# soldering_station_controls.net
KiCad netlist of a schematic drawn in Altium Designer
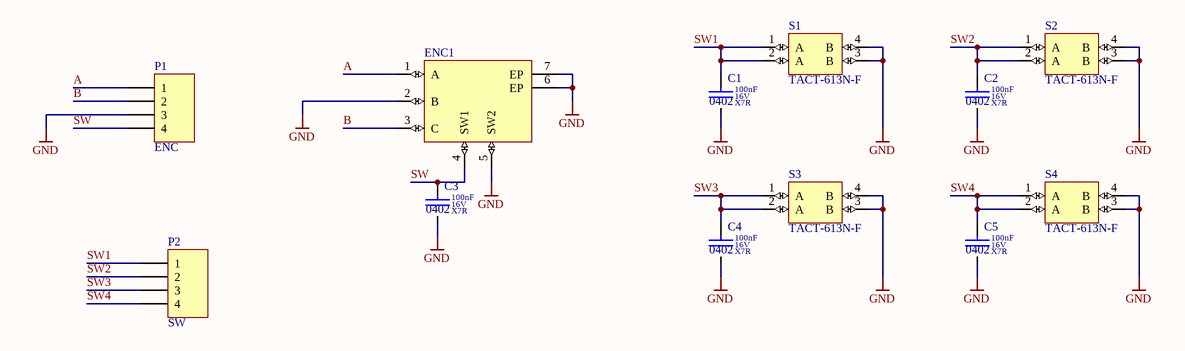
[diagram p0: soldering_station_controls.SchDoc]

(export (version "E")
  (design (tool "Eeschema 10.0.6"))
  (components
    (comp (ref "C1")
      (value "100nF")
      (footprint "C_0402_1005")
      (description "Capacitor")
      (fields
        (field (name "DIELECTRIC") "X7R")
        (field (name "VOLTAGE") "16V")
        (field (name "SCH_FOOTPRINT") "0402")
        (field (name "PART NUMBER") "C_100nF_16V_X7R_0402_10")
        (field (name "MANUFACTURER") "Murata")
      )
      (libsource (lib "Library") (part "C"))
    )
    (comp (ref "C2")
      (value "100nF")
      (footprint "C_0402_1005")
      (description "Capacitor")
      (fields
        (field (name "DIELECTRIC") "X7R")
        (field (name "VOLTAGE") "16V")
        (field (name "SCH_FOOTPRINT") "0402")
        (field (name "PART NUMBER") "C_100nF_16V_X7R_0402_10")
        (field (name "MANUFACTURER") "Murata")
      )
      (libsource (lib "Library") (part "C"))
    )
    (comp (ref "C3")
      (value "100nF")
      (footprint "C_0402_1005")
      (description "Capacitor")
      (fields
        (field (name "DIELECTRIC") "X7R")
        (field (name "VOLTAGE") "16V")
        (field (name "SCH_FOOTPRINT") "0402")
        (field (name "PART NUMBER") "C_100nF_16V_X7R_0402_10")
        (field (name "MANUFACTURER") "Murata")
      )
      (libsource (lib "Library") (part "C"))
    )
    (comp (ref "C4")
      (value "100nF")
      (footprint "C_0402_1005")
      (description "Capacitor")
      (fields
        (field (name "DIELECTRIC") "X7R")
        (field (name "VOLTAGE") "16V")
        (field (name "SCH_FOOTPRINT") "0402")
        (field (name "PART NUMBER") "C_100nF_16V_X7R_0402_10")
        (field (name "MANUFACTURER") "Murata")
      )
      (libsource (lib "Library") (part "C"))
    )
    (comp (ref "C5")
      (value "100nF")
      (footprint "C_0402_1005")
      (description "Capacitor")
      (fields
        (field (name "DIELECTRIC") "X7R")
        (field (name "VOLTAGE") "16V")
        (field (name "SCH_FOOTPRINT") "0402")
        (field (name "PART NUMBER") "C_100nF_16V_X7R_0402_10")
        (field (name "MANUFACTURER") "Murata")
      )
      (libsource (lib "Library") (part "C"))
    )
    (comp (ref "ENC1")
      (value "Wurth Elektronik 482016514001")
      (footprint "ENCODER")
      (libsource (lib "soldering_station") (part "ENCODER"))
    )
    (comp (ref "P1")
      (value "ENC")
      (footprint "P_HEADER_1x4_2.54")
      (description "Header, 4-Pin")
      (fields (field (name "PART NUMBER") "P_HEADER_1x4_2.54") (field (name "MANUFACTURER") "Connfly"))
      (libsource (lib "Library") (part "P_HEADER_1x4"))
    )
    (comp (ref "P2")
      (value "SW")
      (footprint "P_HEADER_1x4_2.54")
      (description "Header, 4-Pin")
      (fields (field (name "PART NUMBER") "P_HEADER_1x4_2.54") (field (name "MANUFACTURER") "Connfly"))
      (libsource (lib "Library") (part "P_HEADER_1x4"))
    )
    (comp (ref "S1")
      (value "TACT-613N-F")
      (footprint "TACT-613N-F")
      (libsource (lib "soldering_station") (part "TACT-613N-F"))
    )
    (comp (ref "S2")
      (value "TACT-613N-F")
      (footprint "TACT-613N-F")
      (libsource (lib "soldering_station") (part "TACT-613N-F"))
    )
    (comp (ref "S3")
      (value "TACT-613N-F")
      (footprint "TACT-613N-F")
      (libsource (lib "soldering_station") (part "TACT-613N-F"))
    )
    (comp (ref "S4")
      (value "TACT-613N-F")
      (footprint "TACT-613N-F")
      (libsource (lib "soldering_station") (part "TACT-613N-F"))
    )
  )
  (nets
    (net (code "1") (name "/A") (class "Default")
      (node (ref "ENC1") (pin "1") (pinfunction "A_1") (pintype "bidirectional"))
      (node (ref "P1") (pin "1") (pinfunction "1_1") (pintype "passive"))
    )
    (net (code "2") (name "/B") (class "Default")
      (node (ref "ENC1") (pin "3") (pinfunction "C_3") (pintype "bidirectional"))
      (node (ref "P1") (pin "2") (pinfunction "2_2") (pintype "passive"))
    )
    (net (code "3") (name "/SW") (class "Default")
      (node (ref "C3") (pin "1") (pinfunction "1_1") (pintype "passive"))
      (node (ref "ENC1") (pin "4") (pinfunction "SW1_4") (pintype "bidirectional"))
      (node (ref "P1") (pin "4") (pinfunction "4_4") (pintype "passive"))
    )
    (net (code "4") (name "/SW1") (class "Default")
      (node (ref "C1") (pin "1") (pinfunction "1_1") (pintype "passive"))
      (node (ref "P2") (pin "1") (pinfunction "1_1") (pintype "passive"))
      (node (ref "S1") (pin "1") (pinfunction "A_1") (pintype "bidirectional"))
      (node (ref "S1") (pin "2") (pinfunction "A_2") (pintype "bidirectional"))
    )
    (net (code "5") (name "/SW2") (class "Default")
      (node (ref "C2") (pin "1") (pinfunction "1_1") (pintype "passive"))
      (node (ref "P2") (pin "2") (pinfunction "2_2") (pintype "passive"))
      (node (ref "S2") (pin "1") (pinfunction "A_1") (pintype "bidirectional"))
      (node (ref "S2") (pin "2") (pinfunction "A_2") (pintype "bidirectional"))
    )
    (net (code "6") (name "/SW3") (class "Default")
      (node (ref "C4") (pin "1") (pinfunction "1_1") (pintype "passive"))
      (node (ref "P2") (pin "3") (pinfunction "3_3") (pintype "passive"))
      (node (ref "S3") (pin "1") (pinfunction "A_1") (pintype "bidirectional"))
      (node (ref "S3") (pin "2") (pinfunction "A_2") (pintype "bidirectional"))
    )
    (net (code "7") (name "/SW4") (class "Default")
      (node (ref "C5") (pin "1") (pinfunction "1_1") (pintype "passive"))
      (node (ref "P2") (pin "4") (pinfunction "4_4") (pintype "passive"))
      (node (ref "S4") (pin "1") (pinfunction "A_1") (pintype "bidirectional"))
      (node (ref "S4") (pin "2") (pinfunction "A_2") (pintype "bidirectional"))
    )
    (net (code "8") (name "GND") (class "Default")
      (node (ref "C1") (pin "2") (pinfunction "2_2") (pintype "passive"))
      (node (ref "C2") (pin "2") (pinfunction "2_2") (pintype "passive"))
      (node (ref "C3") (pin "2") (pinfunction "2_2") (pintype "passive"))
      (node (ref "C4") (pin "2") (pinfunction "2_2") (pintype "passive"))
      (node (ref "C5") (pin "2") (pinfunction "2_2") (pintype "passive"))
      (node (ref "ENC1") (pin "2") (pinfunction "B_2") (pintype "bidirectional"))
      (node (ref "ENC1") (pin "5") (pinfunction "SW2_5") (pintype "bidirectional"))
      (node (ref "ENC1") (pin "6") (pinfunction "EP_6") (pintype "passive"))
      (node (ref "ENC1") (pin "7") (pinfunction "EP_7") (pintype "passive"))
      (node (ref "P1") (pin "3") (pinfunction "3_3") (pintype "passive"))
      (node (ref "S1") (pin "3") (pinfunction "B_3") (pintype "bidirectional"))
      (node (ref "S1") (pin "4") (pinfunction "B_4") (pintype "bidirectional"))
      (node (ref "S2") (pin "3") (pinfunction "B_3") (pintype "bidirectional"))
      (node (ref "S2") (pin "4") (pinfunction "B_4") (pintype "bidirectional"))
      (node (ref "S3") (pin "3") (pinfunction "B_3") (pintype "bidirectional"))
      (node (ref "S3") (pin "4") (pinfunction "B_4") (pintype "bidirectional"))
      (node (ref "S4") (pin "3") (pinfunction "B_3") (pintype "bidirectional"))
      (node (ref "S4") (pin "4") (pinfunction "B_4") (pintype "bidirectional"))
    )
  )
)
